# Cap_array_with_Current_Limiter_V1p0.net
KiCad netlist of a schematic drawn in EAGLE
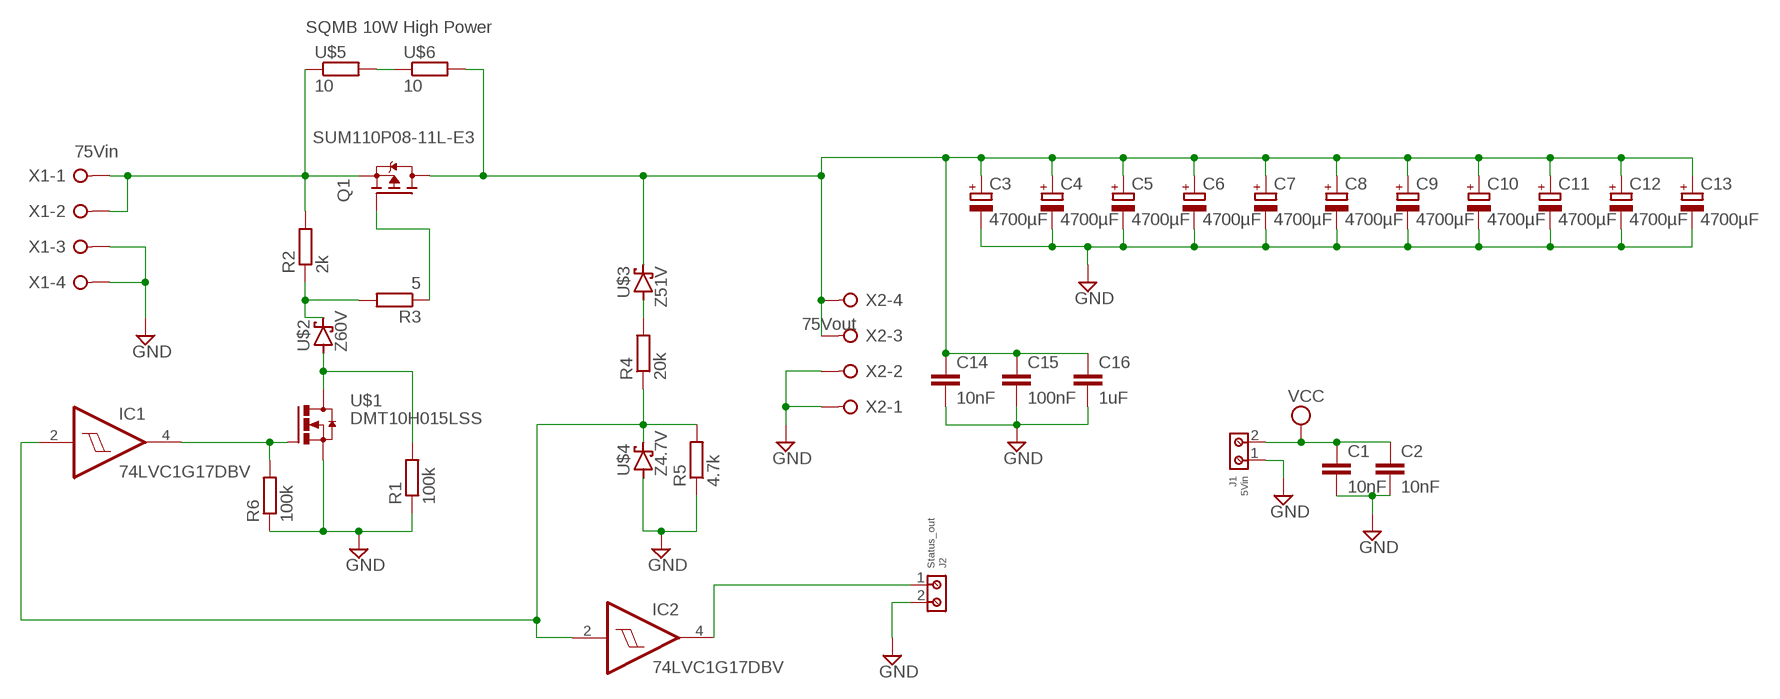
[diagram p0: schematic, sheet 1]

(export (version "E")
  (design (tool "Eeschema 10.0.6"))
  (components
    (comp (ref "C1")
      (value "10nF")
      (footprint "eagle-import:C0805")
      (libsource (lib "eagle-import") (part "C-EUC0805"))
    )
    (comp (ref "C2")
      (value "10nF")
      (footprint "eagle-import:C0805")
      (libsource (lib "eagle-import") (part "C-EUC0805"))
    )
    (comp (ref "C3")
      (value "4700µF")
      (footprint "eagle-import:EB30D")
      (libsource (lib "eagle-import") (part "CPOL-EUE10-30"))
    )
    (comp (ref "C4")
      (value "4700µF")
      (footprint "eagle-import:EB30D")
      (libsource (lib "eagle-import") (part "CPOL-EUE10-30"))
    )
    (comp (ref "C5")
      (value "4700µF")
      (footprint "eagle-import:EB30D")
      (libsource (lib "eagle-import") (part "CPOL-EUE10-30"))
    )
    (comp (ref "C6")
      (value "4700µF")
      (footprint "eagle-import:EB30D")
      (libsource (lib "eagle-import") (part "CPOL-EUE10-30"))
    )
    (comp (ref "C7")
      (value "4700µF")
      (footprint "eagle-import:EB30D")
      (libsource (lib "eagle-import") (part "CPOL-EUE10-30"))
    )
    (comp (ref "C8")
      (value "4700µF")
      (footprint "eagle-import:EB30D")
      (libsource (lib "eagle-import") (part "CPOL-EUE10-30"))
    )
    (comp (ref "C9")
      (value "4700µF")
      (footprint "eagle-import:EB30D")
      (libsource (lib "eagle-import") (part "CPOL-EUE10-30"))
    )
    (comp (ref "C10")
      (value "4700µF")
      (footprint "eagle-import:EB30D")
      (libsource (lib "eagle-import") (part "CPOL-EUE10-30"))
    )
    (comp (ref "C11")
      (value "4700µF")
      (footprint "eagle-import:EB30D")
      (libsource (lib "eagle-import") (part "CPOL-EUE10-30"))
    )
    (comp (ref "C12")
      (value "4700µF")
      (footprint "eagle-import:EB30D")
      (libsource (lib "eagle-import") (part "CPOL-EUE10-30"))
    )
    (comp (ref "C13")
      (value "4700µF")
      (footprint "eagle-import:EB30D")
      (libsource (lib "eagle-import") (part "CPOL-EUE10-30"))
    )
    (comp (ref "C14")
      (value "10nF")
      (footprint "eagle-import:C1206")
      (libsource (lib "eagle-import") (part "C-EUC1206"))
    )
    (comp (ref "C15")
      (value "100nF")
      (footprint "eagle-import:C1206")
      (libsource (lib "eagle-import") (part "C-EUC1206"))
    )
    (comp (ref "C16")
      (value "1uF")
      (footprint "eagle-import:C1206")
      (libsource (lib "eagle-import") (part "C-EUC1206"))
    )
    (comp (ref "IC1")
      (value "74LVC1G17DBV")
      (footprint "eagle-import:SOT23-5")
      (libsource (lib "eagle-import") (part "741G17DBVLVC"))
    )
    (comp (ref "IC2")
      (value "74LVC1G17DBV")
      (footprint "eagle-import:SOT23-5")
      (libsource (lib "eagle-import") (part "741G17DBVLVC"))
    )
    (comp (ref "J1")
      (value "5Vin")
      (footprint "eagle-import:691210910002")
      (libsource (lib "eagle-import") (part "691210910002"))
    )
    (comp (ref "J2")
      (value "Status_out")
      (footprint "eagle-import:691210910002")
      (libsource (lib "eagle-import") (part "691210910002"))
    )
    (comp (ref "Q1")
      (value "SUM110P08-11L-E3")
      (footprint "eagle-import:TO263")
      (libsource (lib "eagle-import") (part "SPB80P06P"))
    )
    (comp (ref "R1")
      (value "100k")
      (footprint "eagle-import:R0805")
      (libsource (lib "eagle-import") (part "R-EU_R0805"))
    )
    (comp (ref "R2")
      (value "2k")
      (footprint "eagle-import:R2512")
      (libsource (lib "eagle-import") (part "R-EU_R2512"))
    )
    (comp (ref "R3")
      (value "5")
      (footprint "eagle-import:R0805")
      (libsource (lib "eagle-import") (part "R-EU_R0805"))
    )
    (comp (ref "R4")
      (value "20k")
      (footprint "eagle-import:R0805")
      (libsource (lib "eagle-import") (part "R-EU_R0805"))
    )
    (comp (ref "R5")
      (value "4.7k")
      (footprint "eagle-import:R0805")
      (libsource (lib "eagle-import") (part "R-EU_R0805"))
    )
    (comp (ref "R6")
      (value "100k")
      (footprint "eagle-import:R0805")
      (libsource (lib "eagle-import") (part "R-EU_R0805"))
    )
    (comp (ref "U$1")
      (value "DMT10H015LSS")
      (footprint "eagle-import:SOIC8")
      (libsource (lib "eagle-import") (part "DMT10H015LSS"))
    )
    (comp (ref "U$2")
      (value "Z60V")
      (footprint "eagle-import:DO-214AA")
      (libsource (lib "eagle-import") (part "SCHOTTKYDO-214-AA"))
    )
    (comp (ref "U$3")
      (value "Z51V")
      (footprint "eagle-import:DO-214AA")
      (libsource (lib "eagle-import") (part "SCHOTTKYDO-214-AA"))
    )
    (comp (ref "U$4")
      (value "Z4.7V")
      (footprint "eagle-import:DO-214AA")
      (libsource (lib "eagle-import") (part "SCHOTTKYDO-214-AA"))
    )
    (comp (ref "U$5")
      (value "10")
      (footprint "eagle-import:SQMB")
      (libsource (lib "eagle-import") (part "SQMB"))
    )
    (comp (ref "U$6")
      (value "10")
      (footprint "eagle-import:SQMB")
      (libsource (lib "eagle-import") (part "SQMB"))
    )
    (comp (ref "X1")
      (value "75Vin")
      (footprint "eagle-import:W237-4P")
      (libsource (lib "eagle-import") (part "W237-04P"))
    )
    (comp (ref "X2")
      (value "75Vout")
      (footprint "eagle-import:W237-4P")
      (libsource (lib "eagle-import") (part "W237-04P"))
    )
  )
  (nets
    (net (code "1") (name "GND") (class "Default")
      (node (ref "C1") (pin "2") (pinfunction "2_2") (pintype "passive"))
      (node (ref "C10") (pin "-") (pinfunction "-_-") (pintype "passive"))
      (node (ref "C11") (pin "-") (pinfunction "-_-") (pintype "passive"))
      (node (ref "C12") (pin "-") (pinfunction "-_-") (pintype "passive"))
      (node (ref "C13") (pin "-") (pinfunction "-_-") (pintype "passive"))
      (node (ref "C14") (pin "2") (pinfunction "2_2") (pintype "passive"))
      (node (ref "C15") (pin "2") (pinfunction "2_2") (pintype "passive"))
      (node (ref "C16") (pin "2") (pinfunction "2_2") (pintype "passive"))
      (node (ref "C2") (pin "2") (pinfunction "2_2") (pintype "passive"))
      (node (ref "C3") (pin "-") (pinfunction "-_-") (pintype "passive"))
      (node (ref "C4") (pin "-") (pinfunction "-_-") (pintype "passive"))
      (node (ref "C5") (pin "-") (pinfunction "-_-") (pintype "passive"))
      (node (ref "C6") (pin "-") (pinfunction "-_-") (pintype "passive"))
      (node (ref "C7") (pin "-") (pinfunction "-_-") (pintype "passive"))
      (node (ref "C8") (pin "-") (pinfunction "-_-") (pintype "passive"))
      (node (ref "C9") (pin "-") (pinfunction "-_-") (pintype "passive"))
      (node (ref "J1") (pin "1") (pinfunction "1_1") (pintype "passive"))
      (node (ref "J2") (pin "2") (pinfunction "2_2") (pintype "passive"))
      (node (ref "R1") (pin "1") (pinfunction "1_1") (pintype "passive"))
      (node (ref "R5") (pin "1") (pinfunction "1_1") (pintype "passive"))
      (node (ref "R6") (pin "1") (pinfunction "1_1") (pintype "passive"))
      (node (ref "U$1") (pin "1") (pinfunction "S_1") (pintype "passive"))
      (node (ref "U$1") (pin "2") (pinfunction "S_2") (pintype "passive"))
      (node (ref "U$1") (pin "3") (pinfunction "S_3") (pintype "passive"))
      (node (ref "U$4") (pin "A") (pinfunction "A_A") (pintype "passive"))
      (node (ref "X1") (pin "3") (pinfunction "KL_3") (pintype "passive"))
      (node (ref "X1") (pin "4") (pinfunction "KL_4") (pintype "passive"))
      (node (ref "X2") (pin "1") (pinfunction "KL_1") (pintype "passive"))
      (node (ref "X2") (pin "2") (pinfunction "KL_2") (pintype "passive"))
    )
    (net (code "2") (name "Net-(IC1A-I)") (class "Default")
      (node (ref "IC1") (pin "2") (pinfunction "I_2") (pintype "input"))
      (node (ref "IC2") (pin "2") (pinfunction "I_2") (pintype "input"))
      (node (ref "R4") (pin "1") (pinfunction "1_1") (pintype "passive"))
      (node (ref "R5") (pin "2") (pinfunction "2_2") (pintype "passive"))
      (node (ref "U$4") (pin "C") (pinfunction "C_C") (pintype "passive"))
    )
    (net (code "3") (name "Net-(IC1A-O)") (class "Default")
      (node (ref "IC1") (pin "4") (pinfunction "O_4") (pintype "output"))
      (node (ref "R6") (pin "2") (pinfunction "2_2") (pintype "passive"))
      (node (ref "U$1") (pin "4") (pinfunction "G_4") (pintype "passive"))
    )
    (net (code "4") (name "Net-(IC2A-O)") (class "Default")
      (node (ref "IC2") (pin "4") (pinfunction "O_4") (pintype "output"))
      (node (ref "J2") (pin "1") (pinfunction "1_1") (pintype "passive"))
    )
    (net (code "5") (name "Net-(Q1-D)") (class "Default")
      (node (ref "C10") (pin "+") (pinfunction "+_+") (pintype "passive"))
      (node (ref "C11") (pin "+") (pinfunction "+_+") (pintype "passive"))
      (node (ref "C12") (pin "+") (pinfunction "+_+") (pintype "passive"))
      (node (ref "C13") (pin "+") (pinfunction "+_+") (pintype "passive"))
      (node (ref "C14") (pin "1") (pinfunction "1_1") (pintype "passive"))
      (node (ref "C15") (pin "1") (pinfunction "1_1") (pintype "passive"))
      (node (ref "C16") (pin "1") (pinfunction "1_1") (pintype "passive"))
      (node (ref "C3") (pin "+") (pinfunction "+_+") (pintype "passive"))
      (node (ref "C4") (pin "+") (pinfunction "+_+") (pintype "passive"))
      (node (ref "C5") (pin "+") (pinfunction "+_+") (pintype "passive"))
      (node (ref "C6") (pin "+") (pinfunction "+_+") (pintype "passive"))
      (node (ref "C7") (pin "+") (pinfunction "+_+") (pintype "passive"))
      (node (ref "C8") (pin "+") (pinfunction "+_+") (pintype "passive"))
      (node (ref "C9") (pin "+") (pinfunction "+_+") (pintype "passive"))
      (node (ref "Q1") (pin "3") (pinfunction "D_3") (pintype "passive"))
      (node (ref "U$3") (pin "C") (pinfunction "C_C") (pintype "passive"))
      (node (ref "U$6") (pin "P$2") (pinfunction "2_P$2") (pintype "passive"))
      (node (ref "X2") (pin "3") (pinfunction "KL_3") (pintype "passive"))
      (node (ref "X2") (pin "4") (pinfunction "KL_4") (pintype "passive"))
    )
    (net (code "6") (name "Net-(Q1-G)") (class "Default")
      (node (ref "Q1") (pin "1") (pinfunction "G_1") (pintype "passive"))
      (node (ref "R3") (pin "1") (pinfunction "1_1") (pintype "passive"))
    )
    (net (code "7") (name "Net-(Q1-S)") (class "Default")
      (node (ref "Q1") (pin "2") (pinfunction "S_2") (pintype "passive"))
      (node (ref "R2") (pin "2") (pinfunction "2_2") (pintype "passive"))
      (node (ref "U$5") (pin "P$1") (pinfunction "1_P$1") (pintype "passive"))
      (node (ref "X1") (pin "1") (pinfunction "KL_1") (pintype "passive"))
      (node (ref "X1") (pin "2") (pinfunction "KL_2") (pintype "passive"))
    )
    (net (code "8") (name "Net-(R1-Pad2)") (class "Default")
      (node (ref "R1") (pin "2") (pinfunction "2_2") (pintype "passive"))
      (node (ref "U$1") (pin "5") (pinfunction "D_5") (pintype "passive"))
      (node (ref "U$1") (pin "6") (pinfunction "D_6") (pintype "passive"))
      (node (ref "U$1") (pin "7") (pinfunction "D_7") (pintype "passive"))
      (node (ref "U$1") (pin "8") (pinfunction "D_8") (pintype "passive"))
      (node (ref "U$2") (pin "A") (pinfunction "A_A") (pintype "passive"))
    )
    (net (code "9") (name "Net-(R2-Pad1)") (class "Default")
      (node (ref "R2") (pin "1") (pinfunction "1_1") (pintype "passive"))
      (node (ref "R3") (pin "2") (pinfunction "2_2") (pintype "passive"))
      (node (ref "U$2") (pin "C") (pinfunction "C_C") (pintype "passive"))
    )
    (net (code "10") (name "Net-(R4-Pad2)") (class "Default")
      (node (ref "R4") (pin "2") (pinfunction "2_2") (pintype "passive"))
      (node (ref "U$3") (pin "A") (pinfunction "A_A") (pintype "passive"))
    )
    (net (code "11") (name "Net-(U$5-2)") (class "Default")
      (node (ref "U$5") (pin "P$2") (pinfunction "2_P$2") (pintype "passive"))
      (node (ref "U$6") (pin "P$1") (pinfunction "1_P$1") (pintype "passive"))
    )
    (net (code "12") (name "VCC") (class "Default")
      (node (ref "C1") (pin "1") (pinfunction "1_1") (pintype "passive"))
      (node (ref "C2") (pin "1") (pinfunction "1_1") (pintype "passive"))
      (node (ref "J1") (pin "2") (pinfunction "2_2") (pintype "passive"))
    )
  )
)
